# Pico_T420_Keyboard.net
KiCad netlist of a schematic drawn in EAGLE
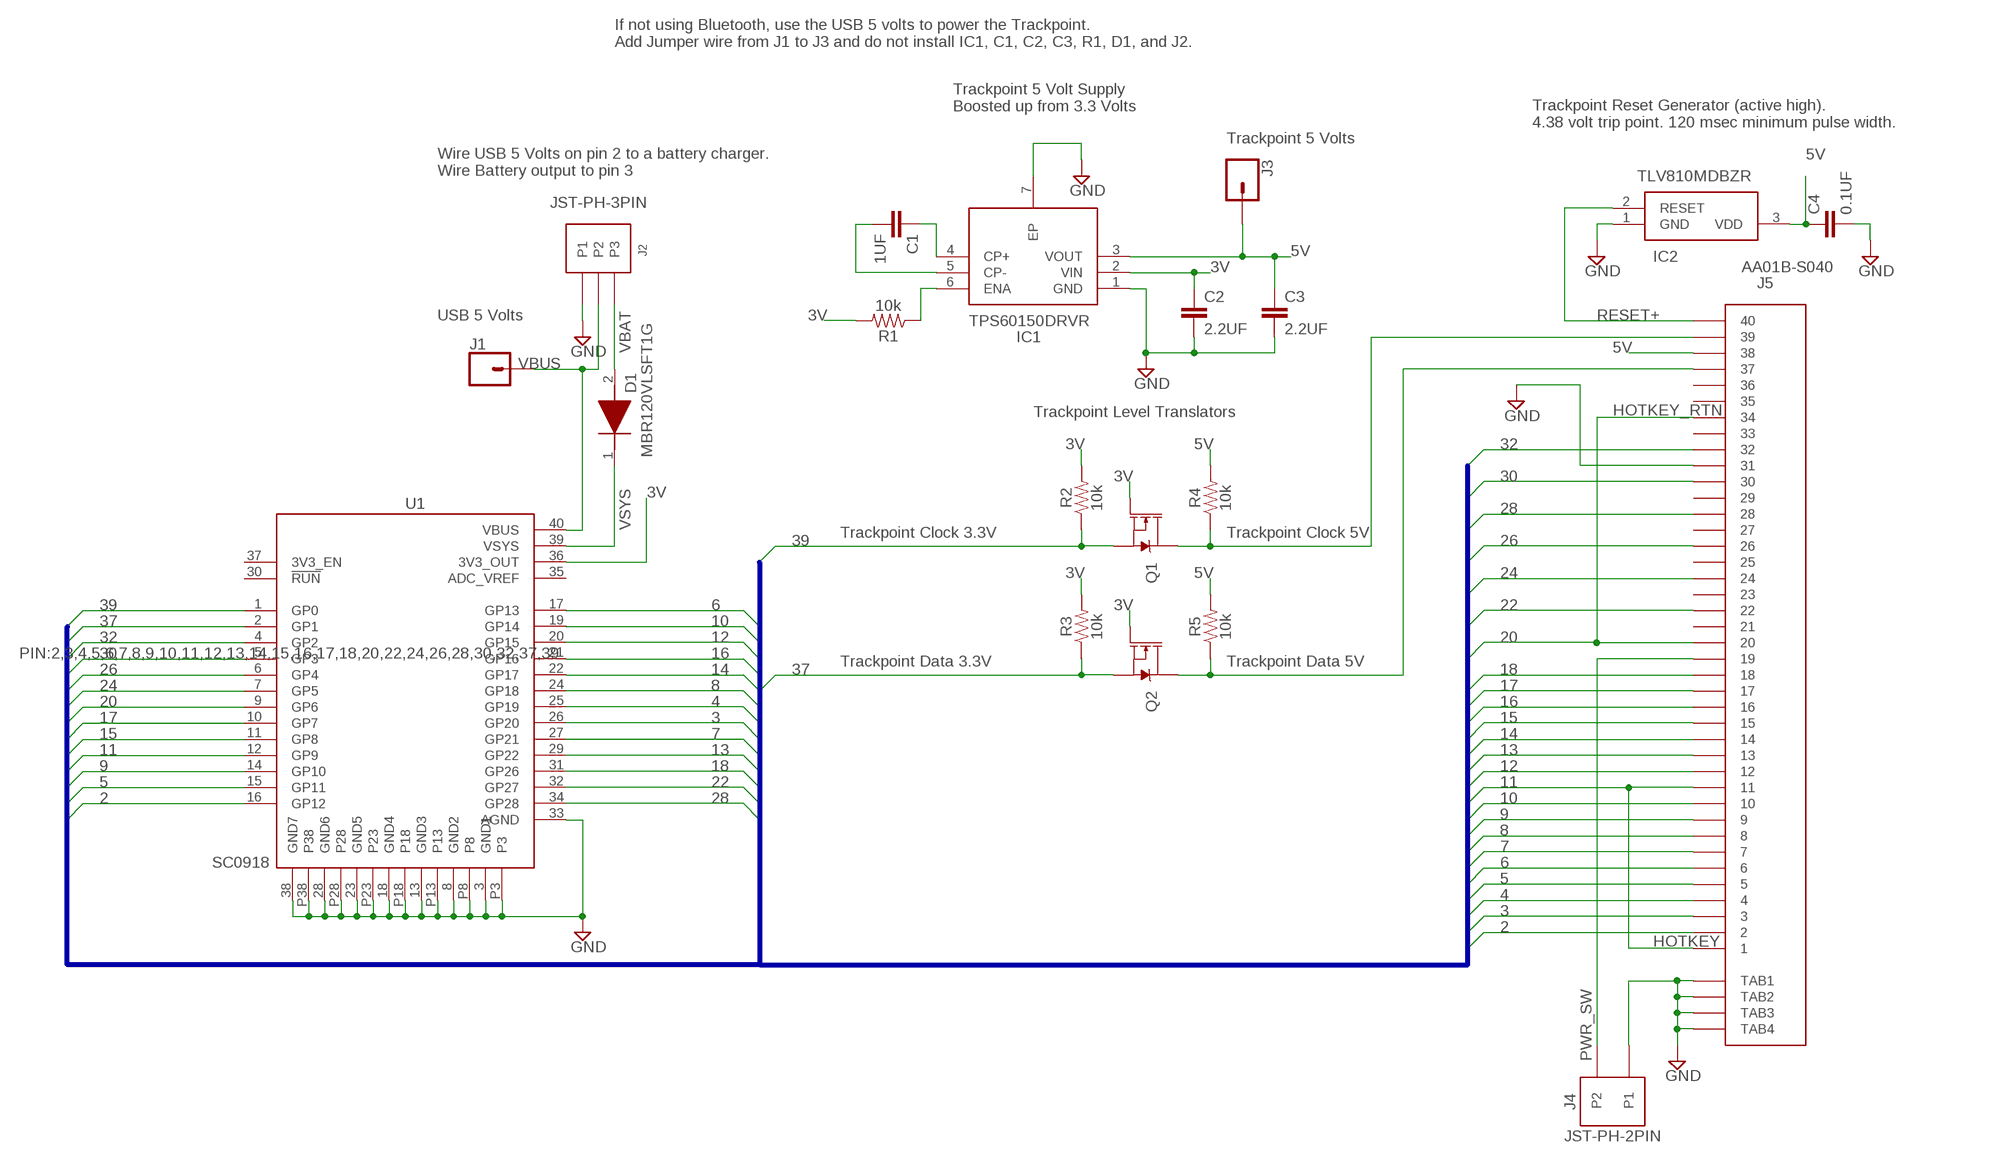
[diagram p0: schematic, sheet 1]

(export (version "E")
  (design (tool "Eeschema 10.0.6"))
  (components
    (comp (ref "C1")
      (value "1UF")
      (footprint "eagle-import:0603_CAP")
      (libsource (lib "eagle-import") (part "0603_CAP"))
    )
    (comp (ref "C2")
      (value "2.2UF")
      (footprint "eagle-import:0603_CAP")
      (libsource (lib "eagle-import") (part "0603_CAP"))
    )
    (comp (ref "C3")
      (value "2.2UF")
      (footprint "eagle-import:0603_CAP")
      (libsource (lib "eagle-import") (part "0603_CAP"))
    )
    (comp (ref "C4")
      (value "0.1UF")
      (footprint "eagle-import:0603_CAP")
      (libsource (lib "eagle-import") (part "0603_CAP"))
    )
    (comp (ref "D1")
      (value "MBR120VLSFT1G")
      (footprint "eagle-import:SODFL3616X98N")
      (fields (field (name "MOUSER_PART_NUMBER") "863-MBR120VLSFT1G"))
      (libsource (lib "eagle-import") (part "MBR120VLSFT1G"))
    )
    (comp (ref "IC1")
      (value "TPS60150DRVR")
      (footprint "eagle-import:SON65P200X200X80-7N")
      (fields (field (name "MOUSER_PART_NUMBER") "595-TPS60150DRVR"))
      (libsource (lib "eagle-import") (part "TPS60150DRVR"))
    )
    (comp (ref "IC2")
      (value "TLV810MDBZR")
      (footprint "eagle-import:SOT95P237X112-3N")
      (fields (field (name "MOUSER_PART_NUMBER") "595-TLV810MDBZR"))
      (libsource (lib "eagle-import") (part "TLV810MDBZR"))
    )
    (comp (ref "J1")
      (value "CONN_01")
      (footprint "eagle-import:1X01")
      (libsource (lib "eagle-import") (part "CONN_01"))
    )
    (comp (ref "J2")
      (value "JST-PH-3PIN")
      (footprint "eagle-import:JST-PH-3PIN")
      (libsource (lib "eagle-import") (part "JST-PH-3PIN"))
    )
    (comp (ref "J3")
      (value "CONN_01")
      (footprint "eagle-import:1X01")
      (libsource (lib "eagle-import") (part "CONN_01"))
    )
    (comp (ref "J4")
      (value "JST-PH-2PIN")
      (footprint "eagle-import:JST-PH-2PIN")
      (libsource (lib "eagle-import") (part "JST-PH-2PIN"))
    )
    (comp (ref "J5")
      (value "AA01B-S040")
      (footprint "eagle-import:WM6787_AA01B")
      (libsource (lib "eagle-import") (part "WM6787_A01B"))
    )
    (comp (ref "Q1")
      (value "220mA/50V/3.5Ω")
      (footprint "eagle-import:SOT23-3")
      (libsource (lib "eagle-import") (part "MOSFET-NCH-BSS138"))
    )
    (comp (ref "Q2")
      (value "220mA/50V/3.5Ω")
      (footprint "eagle-import:SOT23-3")
      (libsource (lib "eagle-import") (part "MOSFET-NCH-BSS138"))
    )
    (comp (ref "R1")
      (value "10k")
      (footprint "eagle-import:0603")
      (libsource (lib "eagle-import") (part "10KOHM-0603-1/10W-1%"))
    )
    (comp (ref "R2")
      (value "10k")
      (footprint "eagle-import:0603")
      (libsource (lib "eagle-import") (part "10KOHM-0603-1/10W-1%"))
    )
    (comp (ref "R3")
      (value "10k")
      (footprint "eagle-import:0603")
      (libsource (lib "eagle-import") (part "10KOHM-0603-1/10W-1%"))
    )
    (comp (ref "R4")
      (value "10k")
      (footprint "eagle-import:0603")
      (libsource (lib "eagle-import") (part "10KOHM-0603-1/10W-1%"))
    )
    (comp (ref "R5")
      (value "10k")
      (footprint "eagle-import:0603")
      (libsource (lib "eagle-import") (part "10KOHM-0603-1/10W-1%"))
    )
    (comp (ref "U1")
      (value "SC0918")
      (footprint "eagle-import:MODULE_SC0918")
      (fields (field (name "MF") "Raspberry Pi"))
      (libsource (lib "eagle-import") (part "SC0918"))
    )
  )
  (nets
    (net (code "2") (name "/2") (class "Default")
      (node (ref "J5") (pin "P$2") (pinfunction "2_P$2") (pintype "bidirectional"))
      (node (ref "U1") (pin "16") (pinfunction "GP12_16") (pintype "bidirectional"))
    )
    (net (code "3") (name "/3") (class "Default")
      (node (ref "J5") (pin "P$3") (pinfunction "3_P$3") (pintype "bidirectional"))
      (node (ref "U1") (pin "26") (pinfunction "GP20_26") (pintype "bidirectional"))
    )
    (net (code "4") (name "/3V") (class "Default")
      (node (ref "C2") (pin "1") (pinfunction "1_1") (pintype "passive"))
      (node (ref "IC1") (pin "2") (pinfunction "VIN_2") (pintype "bidirectional"))
      (node (ref "Q1") (pin "1") (pinfunction "G_1") (pintype "bidirectional"))
      (node (ref "Q2") (pin "1") (pinfunction "G_1") (pintype "bidirectional"))
      (node (ref "R1") (pin "2") (pinfunction "2_2") (pintype "passive"))
      (node (ref "R2") (pin "2") (pinfunction "2_2") (pintype "passive"))
      (node (ref "R3") (pin "2") (pinfunction "2_2") (pintype "passive"))
      (node (ref "U1") (pin "36") (pinfunction "3V3_OUT_36") (pintype "power_in"))
    )
    (net (code "5") (name "/4") (class "Default")
      (node (ref "J5") (pin "P$4") (pinfunction "4_P$4") (pintype "bidirectional"))
      (node (ref "U1") (pin "25") (pinfunction "GP19_25") (pintype "bidirectional"))
    )
    (net (code "6") (name "/5") (class "Default")
      (node (ref "J5") (pin "P$5") (pinfunction "5_P$5") (pintype "bidirectional"))
      (node (ref "U1") (pin "15") (pinfunction "GP11_15") (pintype "bidirectional"))
    )
    (net (code "7") (name "/5V") (class "Default")
      (node (ref "C3") (pin "1") (pinfunction "1_1") (pintype "passive"))
      (node (ref "C4") (pin "1") (pinfunction "1_1") (pintype "passive"))
      (node (ref "IC1") (pin "3") (pinfunction "VOUT_3") (pintype "bidirectional"))
      (node (ref "IC2") (pin "3") (pinfunction "VDD_3") (pintype "bidirectional"))
      (node (ref "J3") (pin "1") (pinfunction "1_1") (pintype "passive"))
      (node (ref "J5") (pin "P$38") (pinfunction "38_P$38") (pintype "bidirectional"))
      (node (ref "R4") (pin "2") (pinfunction "2_2") (pintype "passive"))
      (node (ref "R5") (pin "2") (pinfunction "2_2") (pintype "passive"))
    )
    (net (code "8") (name "/6") (class "Default")
      (node (ref "J5") (pin "P$6") (pinfunction "6_P$6") (pintype "bidirectional"))
      (node (ref "U1") (pin "17") (pinfunction "GP13_17") (pintype "bidirectional"))
    )
    (net (code "9") (name "/7") (class "Default")
      (node (ref "J5") (pin "P$7") (pinfunction "7_P$7") (pintype "bidirectional"))
      (node (ref "U1") (pin "27") (pinfunction "GP21_27") (pintype "bidirectional"))
    )
    (net (code "10") (name "/8") (class "Default")
      (node (ref "J5") (pin "P$8") (pinfunction "8_P$8") (pintype "bidirectional"))
      (node (ref "U1") (pin "24") (pinfunction "GP18_24") (pintype "bidirectional"))
    )
    (net (code "11") (name "/9") (class "Default")
      (node (ref "J5") (pin "P$9") (pinfunction "9_P$9") (pintype "bidirectional"))
      (node (ref "U1") (pin "14") (pinfunction "GP10_14") (pintype "bidirectional"))
    )
    (net (code "12") (name "/10") (class "Default")
      (node (ref "J5") (pin "P$10") (pinfunction "10_P$10") (pintype "bidirectional"))
      (node (ref "U1") (pin "19") (pinfunction "GP14_19") (pintype "bidirectional"))
    )
    (net (code "13") (name "/11") (class "Default")
      (node (ref "J5") (pin "P$1") (pinfunction "1_P$1") (pintype "bidirectional"))
      (node (ref "J5") (pin "P$11") (pinfunction "11_P$11") (pintype "bidirectional"))
      (node (ref "U1") (pin "12") (pinfunction "GP9_12") (pintype "bidirectional"))
    )
    (net (code "14") (name "/12") (class "Default")
      (node (ref "J5") (pin "P$12") (pinfunction "12_P$12") (pintype "bidirectional"))
      (node (ref "U1") (pin "20") (pinfunction "GP15_20") (pintype "bidirectional"))
    )
    (net (code "15") (name "/13") (class "Default")
      (node (ref "J5") (pin "P$13") (pinfunction "13_P$13") (pintype "bidirectional"))
      (node (ref "U1") (pin "29") (pinfunction "GP22_29") (pintype "bidirectional"))
    )
    (net (code "16") (name "/14") (class "Default")
      (node (ref "J5") (pin "P$14") (pinfunction "14_P$14") (pintype "bidirectional"))
      (node (ref "U1") (pin "22") (pinfunction "GP17_22") (pintype "bidirectional"))
    )
    (net (code "17") (name "/15") (class "Default")
      (node (ref "J5") (pin "P$15") (pinfunction "15_P$15") (pintype "bidirectional"))
      (node (ref "U1") (pin "11") (pinfunction "GP8_11") (pintype "bidirectional"))
    )
    (net (code "18") (name "/16") (class "Default")
      (node (ref "J5") (pin "P$16") (pinfunction "16_P$16") (pintype "bidirectional"))
      (node (ref "U1") (pin "21") (pinfunction "GP16_21") (pintype "bidirectional"))
    )
    (net (code "19") (name "/17") (class "Default")
      (node (ref "J5") (pin "P$17") (pinfunction "17_P$17") (pintype "bidirectional"))
      (node (ref "U1") (pin "10") (pinfunction "GP7_10") (pintype "bidirectional"))
    )
    (net (code "20") (name "/18") (class "Default")
      (node (ref "J5") (pin "P$18") (pinfunction "18_P$18") (pintype "bidirectional"))
      (node (ref "U1") (pin "31") (pinfunction "GP26_31") (pintype "bidirectional"))
    )
    (net (code "21") (name "/20") (class "Default")
      (node (ref "J5") (pin "P$20") (pinfunction "20_P$20") (pintype "bidirectional"))
      (node (ref "J5") (pin "P$34") (pinfunction "34_P$34") (pintype "bidirectional"))
      (node (ref "U1") (pin "9") (pinfunction "GP6_9") (pintype "bidirectional"))
    )
    (net (code "22") (name "/22") (class "Default")
      (node (ref "J5") (pin "P$22") (pinfunction "22_P$22") (pintype "bidirectional"))
      (node (ref "U1") (pin "32") (pinfunction "GP27_32") (pintype "bidirectional"))
    )
    (net (code "23") (name "/24") (class "Default")
      (node (ref "J5") (pin "P$24") (pinfunction "24_P$24") (pintype "bidirectional"))
      (node (ref "U1") (pin "7") (pinfunction "GP5_7") (pintype "bidirectional"))
    )
    (net (code "24") (name "/26") (class "Default")
      (node (ref "J5") (pin "P$26") (pinfunction "26_P$26") (pintype "bidirectional"))
      (node (ref "U1") (pin "6") (pinfunction "GP4_6") (pintype "bidirectional"))
    )
    (net (code "25") (name "/28") (class "Default")
      (node (ref "J5") (pin "P$28") (pinfunction "28_P$28") (pintype "bidirectional"))
      (node (ref "U1") (pin "34") (pinfunction "GP28_34") (pintype "bidirectional"))
    )
    (net (code "26") (name "/30") (class "Default")
      (node (ref "J5") (pin "P$30") (pinfunction "30_P$30") (pintype "bidirectional"))
      (node (ref "U1") (pin "5") (pinfunction "GP3_5") (pintype "bidirectional"))
    )
    (net (code "27") (name "/32") (class "Default")
      (node (ref "J5") (pin "P$32") (pinfunction "32_P$32") (pintype "bidirectional"))
      (node (ref "U1") (pin "4") (pinfunction "GP2_4") (pintype "bidirectional"))
    )
    (net (code "28") (name "/37") (class "Default")
      (node (ref "Q2") (pin "2") (pinfunction "S_2") (pintype "bidirectional"))
      (node (ref "R3") (pin "1") (pinfunction "1_1") (pintype "passive"))
      (node (ref "U1") (pin "2") (pinfunction "GP1_2") (pintype "bidirectional"))
    )
    (net (code "29") (name "/39") (class "Default")
      (node (ref "Q1") (pin "2") (pinfunction "S_2") (pintype "bidirectional"))
      (node (ref "R2") (pin "1") (pinfunction "1_1") (pintype "passive"))
      (node (ref "U1") (pin "1") (pinfunction "GP0_1") (pintype "bidirectional"))
    )
    (net (code "30") (name "/ADC_VREF") (class "Default")
      (node (ref "U1") (pin "35") (pinfunction "ADC_VREF_35") (pintype "power_in"))
    )
    (net (code "31") (name "/PWR_SW") (class "Default")
      (node (ref "J4") (pin "P$2") (pinfunction "P2_P$2") (pintype "bidirectional"))
      (node (ref "J5") (pin "P$19") (pinfunction "19_P$19") (pintype "bidirectional"))
    )
    (net (code "32") (name "/RESET+") (class "Default")
      (node (ref "IC2") (pin "2") (pinfunction "RESET_2") (pintype "bidirectional"))
      (node (ref "J5") (pin "P$40") (pinfunction "40_P$40") (pintype "bidirectional"))
    )
    (net (code "33") (name "/VBAT") (class "Default")
      (node (ref "D1") (pin "2") (pinfunction "A_2") (pintype "bidirectional"))
      (node (ref "J2") (pin "P$3") (pinfunction "P3_P$3") (pintype "bidirectional"))
    )
    (net (code "34") (name "/VBUS") (class "Default")
      (node (ref "J1") (pin "1") (pinfunction "1_1") (pintype "passive"))
      (node (ref "J2") (pin "P$2") (pinfunction "P2_P$2") (pintype "bidirectional"))
      (node (ref "U1") (pin "40") (pinfunction "VBUS_40") (pintype "power_in"))
    )
    (net (code "35") (name "/VSYS") (class "Default")
      (node (ref "D1") (pin "1") (pinfunction "K_1") (pintype "bidirectional"))
      (node (ref "U1") (pin "39") (pinfunction "VSYS_39") (pintype "power_in"))
    )
    (net (code "37") (name "GND") (class "Default")
      (node (ref "C2") (pin "2") (pinfunction "2_2") (pintype "passive"))
      (node (ref "C3") (pin "2") (pinfunction "2_2") (pintype "passive"))
      (node (ref "C4") (pin "2") (pinfunction "2_2") (pintype "passive"))
      (node (ref "IC1") (pin "1") (pinfunction "GND_1") (pintype "bidirectional"))
      (node (ref "IC1") (pin "7") (pinfunction "EP_7") (pintype "bidirectional"))
      (node (ref "IC2") (pin "1") (pinfunction "GND_1") (pintype "bidirectional"))
      (node (ref "J2") (pin "P$1") (pinfunction "P1_P$1") (pintype "bidirectional"))
      (node (ref "J4") (pin "P$1") (pinfunction "P1_P$1") (pintype "bidirectional"))
      (node (ref "J5") (pin "P$31") (pinfunction "31_P$31") (pintype "bidirectional"))
      (node (ref "J5") (pin "TAB1") (pinfunction "TAB1_TAB1") (pintype "bidirectional"))
      (node (ref "J5") (pin "TAB2") (pinfunction "TAB2_TAB2") (pintype "bidirectional"))
      (node (ref "J5") (pin "TAB3") (pinfunction "TAB3_TAB3") (pintype "bidirectional"))
      (node (ref "J5") (pin "TAB4") (pinfunction "TAB4_TAB4") (pintype "bidirectional"))
      (node (ref "U1") (pin "13") (pinfunction "GND3_13") (pintype "power_in"))
      (node (ref "U1") (pin "18") (pinfunction "GND4_18") (pintype "power_in"))
      (node (ref "U1") (pin "23") (pinfunction "GND5_23") (pintype "power_in"))
      (node (ref "U1") (pin "28") (pinfunction "GND6_28") (pintype "power_in"))
      (node (ref "U1") (pin "3") (pinfunction "GND1_3") (pintype "power_in"))
      (node (ref "U1") (pin "33") (pinfunction "AGND_33") (pintype "power_in"))
      (node (ref "U1") (pin "38") (pinfunction "GND7_38") (pintype "power_in"))
      (node (ref "U1") (pin "8") (pinfunction "GND2_8") (pintype "power_in"))
      (node (ref "U1") (pin "P13") (pinfunction "P13_P13") (pintype "power_in"))
      (node (ref "U1") (pin "P18") (pinfunction "P18_P18") (pintype "power_in"))
      (node (ref "U1") (pin "P23") (pinfunction "P23_P23") (pintype "power_in"))
      (node (ref "U1") (pin "P28") (pinfunction "P28_P28") (pintype "power_in"))
      (node (ref "U1") (pin "P3") (pinfunction "P3_P3") (pintype "power_in"))
      (node (ref "U1") (pin "P38") (pinfunction "P38_P38") (pintype "power_in"))
      (node (ref "U1") (pin "P8") (pinfunction "P8_P8") (pintype "power_in"))
    )
    (net (code "38") (name "Net-(IC1-CP+)") (class "Default")
      (node (ref "C1") (pin "1") (pinfunction "1_1") (pintype "passive"))
      (node (ref "IC1") (pin "4") (pinfunction "CP+_4") (pintype "bidirectional"))
    )
    (net (code "39") (name "Net-(IC1-CP-)") (class "Default")
      (node (ref "C1") (pin "2") (pinfunction "2_2") (pintype "passive"))
      (node (ref "IC1") (pin "5") (pinfunction "CP-_5") (pintype "bidirectional"))
    )
    (net (code "40") (name "Net-(IC1-ENA)") (class "Default")
      (node (ref "IC1") (pin "6") (pinfunction "ENA_6") (pintype "bidirectional"))
      (node (ref "R1") (pin "1") (pinfunction "1_1") (pintype "passive"))
    )
    (net (code "41") (name "Net-(J5-37)") (class "Default")
      (node (ref "J5") (pin "P$37") (pinfunction "37_P$37") (pintype "bidirectional"))
      (node (ref "Q2") (pin "3") (pinfunction "D_3") (pintype "bidirectional"))
      (node (ref "R5") (pin "1") (pinfunction "1_1") (pintype "passive"))
    )
    (net (code "42") (name "Net-(J5-39)") (class "Default")
      (node (ref "J5") (pin "P$39") (pinfunction "39_P$39") (pintype "bidirectional"))
      (node (ref "Q1") (pin "3") (pinfunction "D_3") (pintype "bidirectional"))
      (node (ref "R4") (pin "1") (pinfunction "1_1") (pintype "passive"))
    )
    (net (code "43") (name "unconnected-(J5-21-PadP$21)") (class "Default")
      (node (ref "J5") (pin "P$21") (pinfunction "21_P$21") (pintype "bidirectional"))
    )
    (net (code "44") (name "unconnected-(J5-23-PadP$23)") (class "Default")
      (node (ref "J5") (pin "P$23") (pinfunction "23_P$23") (pintype "bidirectional"))
    )
    (net (code "45") (name "unconnected-(J5-25-PadP$25)") (class "Default")
      (node (ref "J5") (pin "P$25") (pinfunction "25_P$25") (pintype "bidirectional"))
    )
    (net (code "46") (name "unconnected-(J5-27-PadP$27)") (class "Default")
      (node (ref "J5") (pin "P$27") (pinfunction "27_P$27") (pintype "bidirectional"))
    )
    (net (code "47") (name "unconnected-(J5-29-PadP$29)") (class "Default")
      (node (ref "J5") (pin "P$29") (pinfunction "29_P$29") (pintype "bidirectional"))
    )
    (net (code "48") (name "unconnected-(J5-33-PadP$33)") (class "Default")
      (node (ref "J5") (pin "P$33") (pinfunction "33_P$33") (pintype "bidirectional"))
    )
    (net (code "49") (name "unconnected-(J5-35-PadP$35)") (class "Default")
      (node (ref "J5") (pin "P$35") (pinfunction "35_P$35") (pintype "bidirectional"))
    )
    (net (code "50") (name "unconnected-(J5-36-PadP$36)") (class "Default")
      (node (ref "J5") (pin "P$36") (pinfunction "36_P$36") (pintype "bidirectional"))
    )
    (net (code "51") (name "unconnected-(U1-3V3_EN-Pad37)") (class "Default")
      (node (ref "U1") (pin "37") (pinfunction "3V3_EN_37") (pintype "input"))
    )
    (net (code "52") (name "unconnected-(U1-~{RUN}-Pad30)") (class "Default")
      (node (ref "U1") (pin "30") (pinfunction "~{RUN}_30") (pintype "input"))
    )
  )
)
